# Analog_Inputs.net
KiCad netlist of a schematic drawn in Altium Designer
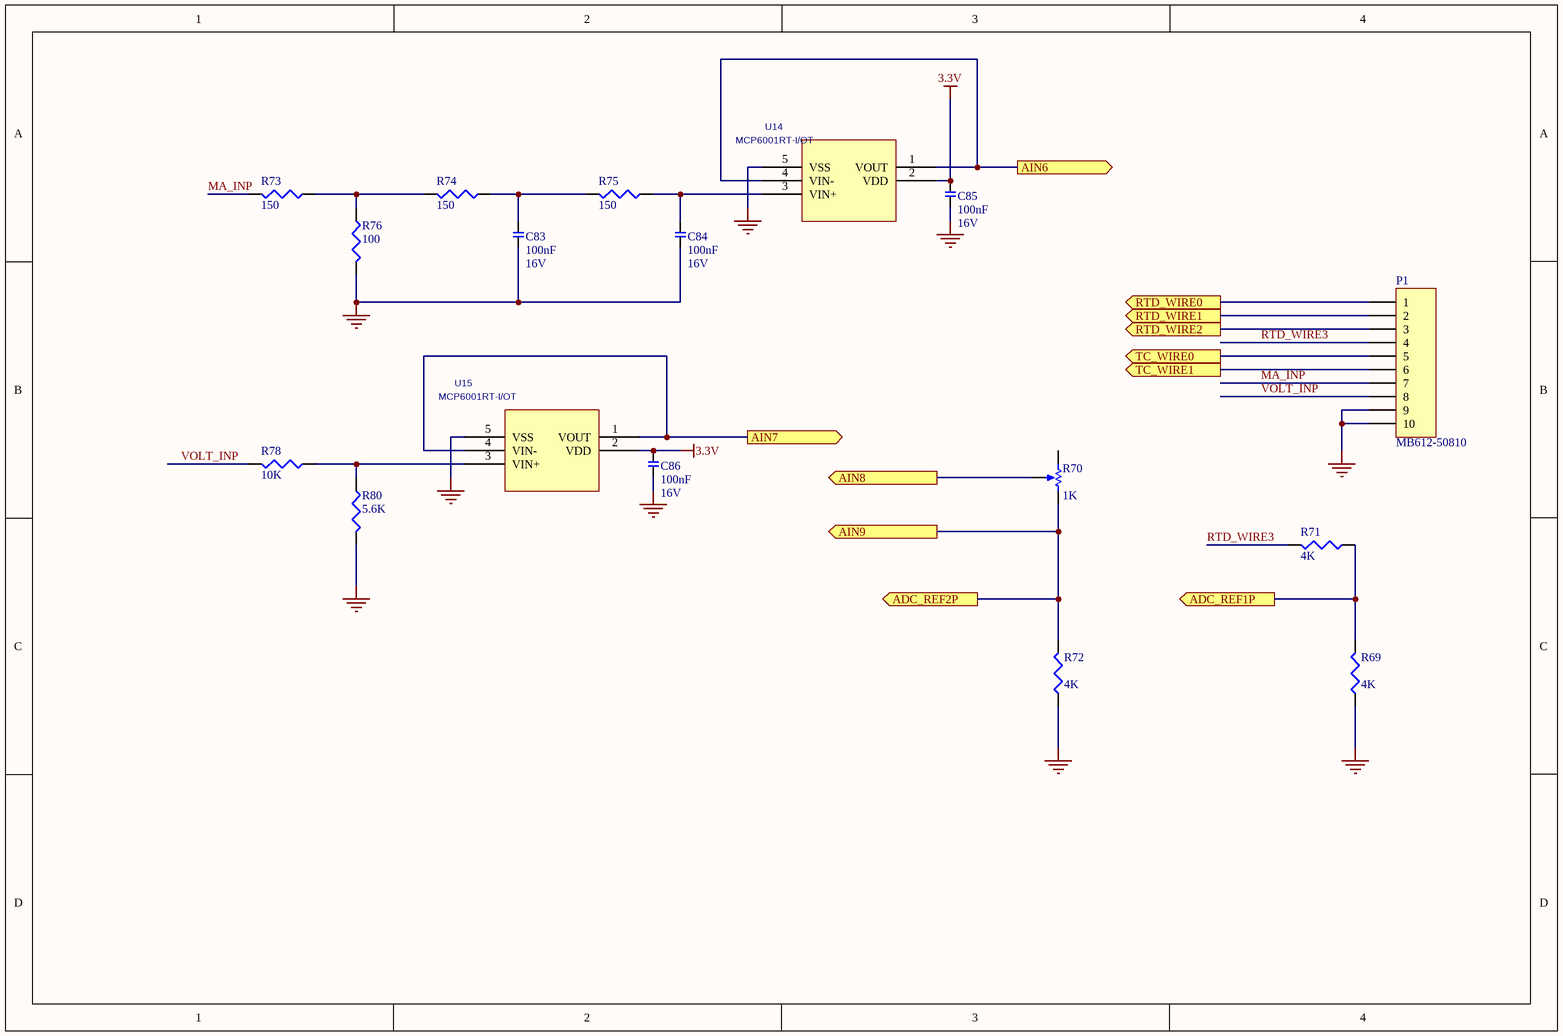
[diagram p0: Analog_Inputs.SchDoc]

(export (version "E")
  (design (tool "Eeschema 10.0.6"))
  (components
    (comp (ref "C83")
      (value "100nF")
      (footprint "T_CAPC0603X33N")
      (description "Capacitor Ceramic X7R 100nF 16V 10% 0603")
      (fields (field (name "TOLERANCE") "10%") (field (name "RATING") "16V"))
      (libsource (lib "Iris") (part "C-X7R-100nF-16V-10%-0603"))
    )
    (comp (ref "C84")
      (value "100nF")
      (footprint "T_CAPC0603X33N")
      (description "Capacitor Ceramic X7R 100nF 16V 10% 0603")
      (fields (field (name "TOLERANCE") "10%") (field (name "RATING") "16V"))
      (libsource (lib "Iris") (part "C-X7R-100nF-16V-10%-0603"))
    )
    (comp (ref "C85")
      (value "100nF")
      (footprint "T_CAPC0603X33N")
      (description "Capacitor Ceramic X7R 100nF 16V 10% 0603")
      (fields (field (name "TOLERANCE") "10%") (field (name "RATING") "16V"))
      (libsource (lib "Iris") (part "C-X7R-100nF-16V-10%-0603"))
    )
    (comp (ref "C86")
      (value "100nF")
      (footprint "T_CAPC0603X33N")
      (description "Capacitor Ceramic X7R 100nF 16V 10% 0603")
      (fields (field (name "TOLERANCE") "10%") (field (name "RATING") "16V"))
      (libsource (lib "Iris") (part "C-X7R-100nF-16V-10%-0603"))
    )
    (comp (ref "P1")
      (value "MB612-50810")
      (footprint "1729186 5.08 - 10pos")
      (description "Header, 10-Pin")
      (fields (field (name "PUBLISHER") "Altium Limited"))
      (libsource (lib "Miscellaneous Connectors") (part "Header 10"))
    )
    (comp (ref "R69")
      (value "4K")
      (footprint "J1-0603")
      (description "Resistor")
      (fields (field (name "Comment") "Res3") (field (name "PUBLISHER") "Altium Limited"))
      (libsource (lib "Miscellaneous Devices") (part "Res3"))
    )
    (comp (ref "R70")
      (value "1K")
      (footprint "VR5")
      (description "Potentiometer")
      (fields (field (name "Comment") "RPot") (field (name "PUBLISHER") "Altium Limited"))
      (libsource (lib "Miscellaneous Devices") (part "RPot"))
    )
    (comp (ref "R71")
      (value "4K")
      (footprint "J1-0603")
      (description "Resistor")
      (fields (field (name "Comment") "Res3") (field (name "PUBLISHER") "Altium Limited"))
      (libsource (lib "Miscellaneous Devices") (part "Res3"))
    )
    (comp (ref "R72")
      (value "4K")
      (footprint "J1-0603")
      (description "Resistor")
      (fields (field (name "Comment") "Res3") (field (name "PUBLISHER") "Altium Limited"))
      (libsource (lib "Miscellaneous Devices") (part "Res3"))
    )
    (comp (ref "R73")
      (value "150")
      (footprint "J1-0603")
      (description "Resistor")
      (fields (field (name "Comment") "Res3") (field (name "PUBLISHER") "Altium Limited"))
      (libsource (lib "Miscellaneous Devices") (part "Res3"))
    )
    (comp (ref "R74")
      (value "150")
      (footprint "J1-0603")
      (description "Resistor")
      (fields (field (name "Comment") "Res3") (field (name "PUBLISHER") "Altium Limited"))
      (libsource (lib "Miscellaneous Devices") (part "Res3"))
    )
    (comp (ref "R75")
      (value "150")
      (footprint "J1-0603")
      (description "Resistor")
      (fields (field (name "Comment") "Res3") (field (name "PUBLISHER") "Altium Limited"))
      (libsource (lib "Miscellaneous Devices") (part "Res3"))
    )
    (comp (ref "R76")
      (value "100")
      (footprint "J1-0603")
      (description "Resistor")
      (fields (field (name "Comment") "Res3") (field (name "PUBLISHER") "Altium Limited"))
      (libsource (lib "Miscellaneous Devices") (part "Res3"))
    )
    (comp (ref "R78")
      (value "10K")
      (footprint "J1-0603")
      (description "Resistor")
      (fields (field (name "Comment") "Res3") (field (name "PUBLISHER") "Altium Limited"))
      (libsource (lib "Miscellaneous Devices") (part "Res3"))
    )
    (comp (ref "R80")
      (value "5.6K")
      (footprint "J1-0603")
      (description "Resistor")
      (fields (field (name "Comment") "Res3") (field (name "PUBLISHER") "Altium Limited"))
      (libsource (lib "Miscellaneous Devices") (part "Res3"))
    )
    (comp (ref "U14")
      (value "MCP6001RT-I/OT")
      (footprint "SOT-23-5")
      (fields (field (name "MANUFACTURER_PART_NUMBER") "mcp6001rt-i/ot"))
      (libsource (lib "Inlib") (part "MCP6001RT-I/OT"))
    )
    (comp (ref "U15")
      (value "MCP6001RT-I/OT")
      (footprint "SOT-23-5")
      (fields (field (name "MANUFACTURER_PART_NUMBER") "mcp6001rt-i/ot"))
      (libsource (lib "Inlib") (part "MCP6001RT-I/OT"))
    )
  )
  (nets
    (net (code "1") (name "/ADC_REF1P") (class "Default")
      (node (ref "R69") (pin "2") (pinfunction "2_2") (pintype "passive"))
      (node (ref "R71") (pin "1") (pinfunction "1_1") (pintype "passive"))
    )
    (net (code "2") (name "/ADC_REF2P") (class "Default")
      (node (ref "R70") (pin "2") (pinfunction "BOT_2") (pintype "passive"))
      (node (ref "R72") (pin "2") (pinfunction "2_2") (pintype "passive"))
    )
    (net (code "3") (name "/AIN6") (class "Default")
      (node (ref "U14") (pin "1") (pinfunction "VOUT_1") (pintype "passive"))
      (node (ref "U14") (pin "4") (pinfunction "VIN-_4") (pintype "passive"))
    )
    (net (code "4") (name "/AIN7") (class "Default")
      (node (ref "U15") (pin "1") (pinfunction "VOUT_1") (pintype "passive"))
      (node (ref "U15") (pin "4") (pinfunction "VIN-_4") (pintype "passive"))
    )
    (net (code "5") (name "/AIN8") (class "Default")
      (node (ref "R70") (pin "3") (pinfunction "TAP_3") (pintype "passive"))
    )
    (net (code "6") (name "/MA_INP") (class "Default")
      (node (ref "P1") (pin "7") (pinfunction "7_7") (pintype "passive"))
      (node (ref "R73") (pin "2") (pinfunction "2_2") (pintype "passive"))
    )
    (net (code "7") (name "/RTD_WIRE0") (class "Default")
      (node (ref "P1") (pin "1") (pinfunction "1_1") (pintype "passive"))
    )
    (net (code "8") (name "/RTD_WIRE1") (class "Default")
      (node (ref "P1") (pin "2") (pinfunction "2_2") (pintype "passive"))
    )
    (net (code "9") (name "/RTD_WIRE2") (class "Default")
      (node (ref "P1") (pin "3") (pinfunction "3_3") (pintype "passive"))
    )
    (net (code "10") (name "/RTD_WIRE3") (class "Default")
      (node (ref "P1") (pin "4") (pinfunction "4_4") (pintype "passive"))
      (node (ref "R71") (pin "2") (pinfunction "2_2") (pintype "passive"))
    )
    (net (code "11") (name "/TC_WIRE0") (class "Default")
      (node (ref "P1") (pin "5") (pinfunction "5_5") (pintype "passive"))
    )
    (net (code "12") (name "/TC_WIRE1") (class "Default")
      (node (ref "P1") (pin "6") (pinfunction "6_6") (pintype "passive"))
    )
    (net (code "13") (name "/VOLT_INP") (class "Default")
      (node (ref "P1") (pin "8") (pinfunction "8_8") (pintype "passive"))
      (node (ref "R78") (pin "2") (pinfunction "2_2") (pintype "passive"))
    )
    (net (code "14") (name "3.3V") (class "Default")
      (node (ref "C85") (pin "2") (pinfunction "2_2") (pintype "passive"))
      (node (ref "C86") (pin "2") (pinfunction "2_2") (pintype "passive"))
      (node (ref "U14") (pin "2") (pinfunction "VDD_2") (pintype "passive"))
      (node (ref "U15") (pin "2") (pinfunction "VDD_2") (pintype "passive"))
    )
    (net (code "15") (name "GND") (class "Default")
      (node (ref "C83") (pin "1") (pinfunction "1_1") (pintype "passive"))
      (node (ref "C84") (pin "1") (pinfunction "1_1") (pintype "passive"))
      (node (ref "C85") (pin "1") (pinfunction "1_1") (pintype "passive"))
      (node (ref "C86") (pin "1") (pinfunction "1_1") (pintype "passive"))
      (node (ref "P1") (pin "10") (pinfunction "10_10") (pintype "passive"))
      (node (ref "P1") (pin "9") (pinfunction "9_9") (pintype "passive"))
      (node (ref "R69") (pin "1") (pinfunction "1_1") (pintype "passive"))
      (node (ref "R72") (pin "1") (pinfunction "1_1") (pintype "passive"))
      (node (ref "R76") (pin "2") (pinfunction "2_2") (pintype "passive"))
      (node (ref "R80") (pin "2") (pinfunction "2_2") (pintype "passive"))
      (node (ref "U14") (pin "5") (pinfunction "VSS_5") (pintype "passive"))
      (node (ref "U15") (pin "5") (pinfunction "VSS_5") (pintype "passive"))
    )
    (net (code "16") (name "Net-(C83-Pad2)") (class "Default")
      (node (ref "C83") (pin "2") (pinfunction "2_2") (pintype "passive"))
      (node (ref "R74") (pin "1") (pinfunction "1_1") (pintype "passive"))
      (node (ref "R75") (pin "2") (pinfunction "2_2") (pintype "passive"))
    )
    (net (code "17") (name "Net-(R73-Pad1)") (class "Default")
      (node (ref "R73") (pin "1") (pinfunction "1_1") (pintype "passive"))
      (node (ref "R74") (pin "2") (pinfunction "2_2") (pintype "passive"))
      (node (ref "R76") (pin "1") (pinfunction "1_1") (pintype "passive"))
    )
    (net (code "18") (name "Net-(U14-VIN+)") (class "Default")
      (node (ref "C84") (pin "2") (pinfunction "2_2") (pintype "passive"))
      (node (ref "R75") (pin "1") (pinfunction "1_1") (pintype "passive"))
      (node (ref "U14") (pin "3") (pinfunction "VIN+_3") (pintype "passive"))
    )
    (net (code "19") (name "Net-(U15-VIN+)") (class "Default")
      (node (ref "R78") (pin "1") (pinfunction "1_1") (pintype "passive"))
      (node (ref "R80") (pin "1") (pinfunction "1_1") (pintype "passive"))
      (node (ref "U15") (pin "3") (pinfunction "VIN+_3") (pintype "passive"))
    )
    (net (code "20") (name "unconnected-(R70-TOP-Pad1)") (class "Default")
      (node (ref "R70") (pin "1") (pinfunction "TOP_1") (pintype "passive"))
    )
  )
)
